# ui-board.net
KiCad netlist of a schematic drawn in Altium Designer
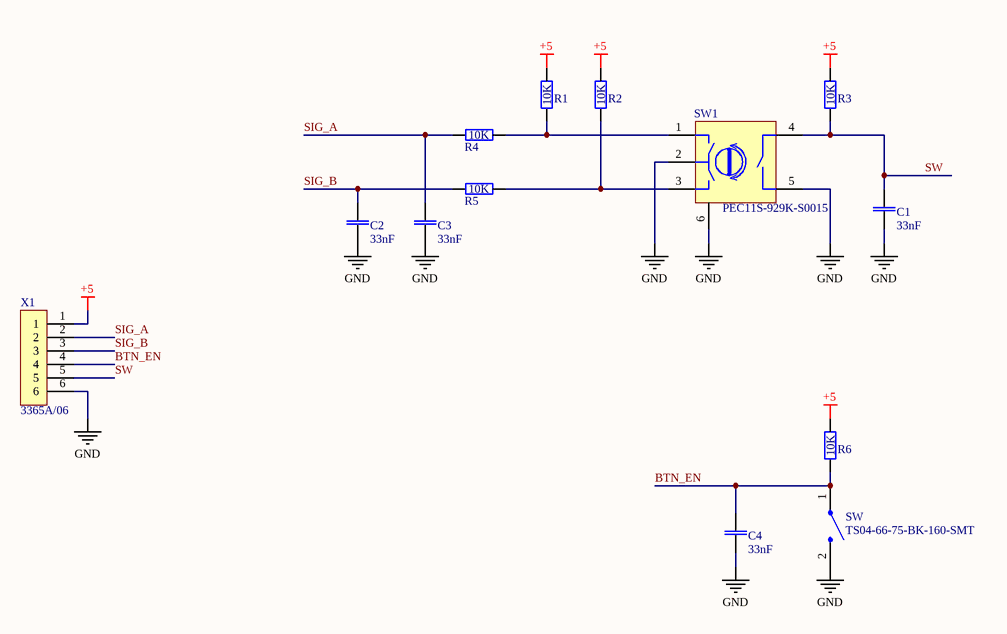
[diagram p0: ui-board.SchDoc]

(export (version "E")
  (design (tool "Eeschema 10.0.6"))
  (components
    (comp (ref "C1")
      (value "33nF")
      (footprint "CAP0402")
      (fields (field (name "MPN") "C0402C333K4RECTU"))
      (libsource (lib "Passive") (part "C0402C333K4RECTU"))
    )
    (comp (ref "C2")
      (value "33nF")
      (footprint "CAP0402")
      (fields (field (name "MPN") "C0402C333K4RECTU"))
      (libsource (lib "Passive") (part "C0402C333K4RECTU"))
    )
    (comp (ref "C3")
      (value "33nF")
      (footprint "CAP0402")
      (fields (field (name "MPN") "C0402C333K4RECTU"))
      (libsource (lib "Passive") (part "C0402C333K4RECTU"))
    )
    (comp (ref "C4")
      (value "33nF")
      (footprint "CAP0402")
      (fields (field (name "MPN") "C0402C333K4RECTU"))
      (libsource (lib "Passive") (part "C0402C333K4RECTU"))
    )
    (comp (ref "R1")
      (value "10K")
      (footprint "RES0402")
      (fields
        (field (name "POWER") "0.063W")
        (field (name "TOLERANCE") "5%")
        (field (name "MPN") "RC0402JR-0710KL")
      )
      (libsource (lib "Passive") (part "RC0402JR-0710KL"))
    )
    (comp (ref "R2")
      (value "10K")
      (footprint "RES0402")
      (fields
        (field (name "POWER") "0.063W")
        (field (name "TOLERANCE") "5%")
        (field (name "MPN") "RC0402JR-0710KL")
      )
      (libsource (lib "Passive") (part "RC0402JR-0710KL"))
    )
    (comp (ref "R3")
      (value "10K")
      (footprint "RES0402")
      (fields
        (field (name "POWER") "0.063W")
        (field (name "TOLERANCE") "5%")
        (field (name "MPN") "RC0402JR-0710KL")
      )
      (libsource (lib "Passive") (part "RC0402JR-0710KL"))
    )
    (comp (ref "R4")
      (value "10K")
      (footprint "RES0402")
      (fields
        (field (name "POWER") "0.063W")
        (field (name "TOLERANCE") "5%")
        (field (name "MPN") "RC0402JR-0710KL")
      )
      (libsource (lib "Passive") (part "RC0402JR-0710KL"))
    )
    (comp (ref "R5")
      (value "10K")
      (footprint "RES0402")
      (fields
        (field (name "POWER") "0.063W")
        (field (name "TOLERANCE") "5%")
        (field (name "MPN") "RC0402JR-0710KL")
      )
      (libsource (lib "Passive") (part "RC0402JR-0710KL"))
    )
    (comp (ref "R6")
      (value "10K")
      (footprint "RES0402")
      (fields
        (field (name "POWER") "0.063W")
        (field (name "TOLERANCE") "5%")
        (field (name "MPN") "RC0402JR-0710KL")
      )
      (libsource (lib "Passive") (part "RC0402JR-0710KL"))
    )
    (comp (ref "SW")
      (value "TS04-66-75-BK-160-SMT")
      (footprint "TS04-66-75-BK-160-SMT")
      (libsource (lib "Schematic") (part "TS04-66-75-BK-160-SMT"))
    )
    (comp (ref "SW1")
      (value "PEC11S-929K-S0015")
      (footprint "PEC11S-929K-S0015")
      (libsource (lib "Schematic") (part "PEC11S-929K-S0015"))
    )
    (comp (ref "X1")
      (value "3365A/06")
      (footprint "3M_CBL_RIBN_6X")
      (libsource (lib "Schematic") (part "3365A/06"))
    )
  )
  (nets
    (net (code "1") (name "+5") (class "Default")
      (node (ref "R1") (pin "2") (pinfunction "2_2") (pintype "passive"))
      (node (ref "R2") (pin "2") (pinfunction "2_2") (pintype "passive"))
      (node (ref "R3") (pin "2") (pinfunction "2_2") (pintype "passive"))
      (node (ref "R6") (pin "2") (pinfunction "2_2") (pintype "passive"))
      (node (ref "X1") (pin "1") (pinfunction "1_1") (pintype "passive"))
    )
    (net (code "2") (name "/BTN_EN") (class "Default")
      (node (ref "C4") (pin "2") (pinfunction "2_2") (pintype "passive"))
      (node (ref "R6") (pin "1") (pinfunction "1_1") (pintype "passive"))
      (node (ref "SW") (pin "1") (pinfunction "1_1") (pintype "passive"))
      (node (ref "X1") (pin "4") (pinfunction "4_4") (pintype "passive"))
    )
    (net (code "3") (name "/SIG_A") (class "Default")
      (node (ref "C3") (pin "2") (pinfunction "2_2") (pintype "passive"))
      (node (ref "R4") (pin "1") (pinfunction "1_1") (pintype "passive"))
      (node (ref "X1") (pin "2") (pinfunction "2_2") (pintype "passive"))
    )
    (net (code "4") (name "/SIG_B") (class "Default")
      (node (ref "C2") (pin "2") (pinfunction "2_2") (pintype "passive"))
      (node (ref "R5") (pin "1") (pinfunction "1_1") (pintype "passive"))
      (node (ref "X1") (pin "3") (pinfunction "3_3") (pintype "passive"))
    )
    (net (code "5") (name "/SW") (class "Default")
      (node (ref "C1") (pin "2") (pinfunction "2_2") (pintype "passive"))
      (node (ref "R3") (pin "1") (pinfunction "1_1") (pintype "passive"))
      (node (ref "SW1") (pin "4") (pinfunction "4_4") (pintype "passive"))
      (node (ref "X1") (pin "5") (pinfunction "5_5") (pintype "passive"))
    )
    (net (code "6") (name "GND") (class "Default")
      (node (ref "C1") (pin "1") (pinfunction "1_1") (pintype "passive"))
      (node (ref "C2") (pin "1") (pinfunction "1_1") (pintype "passive"))
      (node (ref "C3") (pin "1") (pinfunction "1_1") (pintype "passive"))
      (node (ref "C4") (pin "1") (pinfunction "1_1") (pintype "passive"))
      (node (ref "SW") (pin "2") (pinfunction "2_2") (pintype "passive"))
      (node (ref "SW1") (pin "2") (pinfunction "C_2") (pintype "passive"))
      (node (ref "SW1") (pin "5") (pinfunction "5_5") (pintype "passive"))
      (node (ref "SW1") (pin "6") (pinfunction "6_6") (pintype "passive"))
      (node (ref "X1") (pin "6") (pinfunction "6_6") (pintype "passive"))
    )
    (net (code "7") (name "Net-(SW1-A)") (class "Default")
      (node (ref "R1") (pin "1") (pinfunction "1_1") (pintype "passive"))
      (node (ref "R4") (pin "2") (pinfunction "2_2") (pintype "passive"))
      (node (ref "SW1") (pin "1") (pinfunction "A_1") (pintype "passive"))
    )
    (net (code "8") (name "Net-(SW1-B)") (class "Default")
      (node (ref "R2") (pin "1") (pinfunction "1_1") (pintype "passive"))
      (node (ref "R5") (pin "2") (pinfunction "2_2") (pintype "passive"))
      (node (ref "SW1") (pin "3") (pinfunction "B_3") (pintype "passive"))
    )
  )
)
